# Charging_sch.net
KiCad netlist of a schematic drawn in Altium Designer
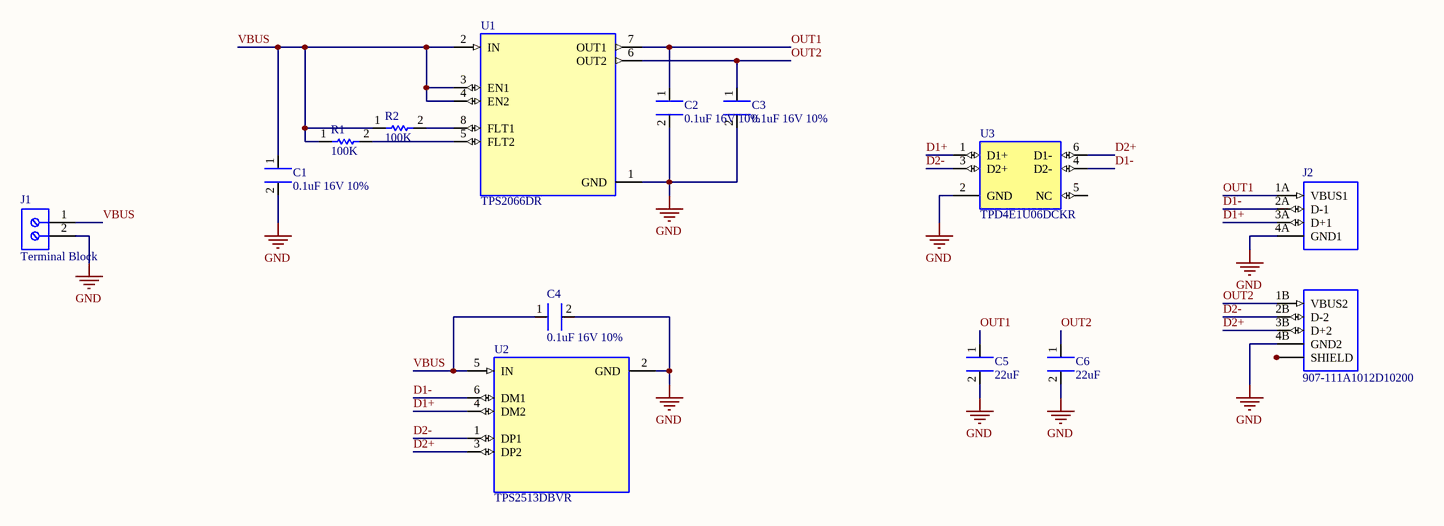
[diagram p0: Charging_sch.SchDoc]

(export (version "E")
  (design (tool "Eeschema 10.0.6"))
  (components
    (comp (ref "C1")
      (value "0.1uF 16V 10%")
      (footprint "CC0805KRX7R9BB104")
      (description "贴片电容（MLCC） 100nF ±10% 50V X7R 0805")
      (fields
        (field (name "MANUFACTURER") "Yageo")
        (field (name "MANUFACTURER PART NUMBER") "CC0805KRX7R9BB104")
      )
      (libsource (lib "Schlib2") (part "CC0805KRX7R9BB104"))
    )
    (comp (ref "C2")
      (value "0.1uF 16V 10%")
      (footprint "CC0805KRX7R9BB104")
      (description "贴片电容（MLCC） 100nF ±10% 50V X7R 0805")
      (fields
        (field (name "MANUFACTURER") "Yageo")
        (field (name "MANUFACTURER PART NUMBER") "CC0805KRX7R9BB104")
      )
      (libsource (lib "Schlib2") (part "CC0805KRX7R9BB104"))
    )
    (comp (ref "C3")
      (value "0.1uF 16V 10%")
      (footprint "CC0805KRX7R9BB104")
      (description "贴片电容（MLCC） 100nF ±10% 50V X7R 0805")
      (fields
        (field (name "MANUFACTURER") "Yageo")
        (field (name "MANUFACTURER PART NUMBER") "CC0805KRX7R9BB104")
      )
      (libsource (lib "Schlib2") (part "CC0805KRX7R9BB104"))
    )
    (comp (ref "C4")
      (value "0.1uF 16V 10%")
      (footprint "CC0805KRX7R9BB104")
      (description "贴片电容（MLCC） 100nF ±10% 50V X7R 0805")
      (fields
        (field (name "MANUFACTURER") "Yageo")
        (field (name "MANUFACTURER PART NUMBER") "CC0805KRX7R9BB104")
      )
      (libsource (lib "Schlib2") (part "CC0805KRX7R9BB104"))
    )
    (comp (ref "C5")
      (value "22uF")
      (footprint "RVT1C220M0405")
      (fields
        (field (name "MANUFACTURER") "ROQANG")
        (field (name "MANUFACTURER PART NUMBER") "RVT1C220M0405")
      )
      (libsource (lib "Schlib2") (part "RVT1C220M0405"))
    )
    (comp (ref "C6")
      (value "22uF")
      (footprint "RVT1C220M0405")
      (fields
        (field (name "MANUFACTURER") "ROQANG")
        (field (name "MANUFACTURER PART NUMBER") "RVT1C220M0405")
      )
      (libsource (lib "Schlib2") (part "RVT1C220M0405"))
    )
    (comp (ref "J1")
      (value "Terminal Block")
      (footprint "Terminal Block")
      (description "Conn Terminal Block F 2 POS 5mm Solder RA SMD 6A T/R")
      (fields
        (field (name "MANUFACTURER") "Wurth Electronics Midcom")
        (field (name "MANUFACTURER PART NUMBER") "691709710302")
      )
      (libsource (lib "Schlib1") (part "691709710302"))
    )
    (comp (ref "J2")
      (value "907-111A1012D10200")
      (footprint "907-111A1012D10200")
      (description "USB1035 Series 8 Position Dual Port Through Hole USB")
      (fields (field (name "MANUFACTURER") "Jing Extension of the Electronic Co."))
      (libsource (lib "Schlib2") (part "907-111A1012D10200"))
    )
    (comp (ref "R1")
      (value "100K")
      (footprint "ARG05FTC1003")
      (fields
        (field (name "MANUFACTURER") "Viking Tech")
        (field (name "MANUFACTURER PART NUMBER") "ARG05FTC1003")
      )
      (libsource (lib "Schlib2") (part "ARG05FTC1003"))
    )
    (comp (ref "R2")
      (value "100K")
      (footprint "ARG05FTC1003")
      (fields
        (field (name "MANUFACTURER") "Viking Tech")
        (field (name "MANUFACTURER PART NUMBER") "ARG05FTC1003")
      )
      (libsource (lib "Schlib2") (part "ARG05FTC1003"))
    )
    (comp (ref "U1")
      (value "TPS2066DR")
      (footprint "TPS2066DR")
      (description "Dual 1A, active-high, current-limited, power-distribution switches 8-SOIC -40 to 85")
      (fields (field (name "MANUFACTURER") "Texas Instruments"))
      (libsource (lib "Schlib2") (part "TPS2066DR"))
    )
    (comp (ref "U2")
      (value "TPS2513DBVR")
      (footprint "TPS2513DBVR")
      (description "USB Charging Port Controller Dual 5.5V 6-Pin SOT-23 T/R / IC USB PWR SW/CTRLR CHRG SOT23-6")
      (fields (field (name "MANUFACTURER") "Texas Instruments"))
      (libsource (lib "Schlib2") (part "TPS2513DBVR"))
    )
    (comp (ref "U3")
      (value "TPD4E1U06DCKR")
      (footprint "TPD4E1U06DCKR")
      (description "TVS DIODE 5.5VWM 15VC SC70-6")
      (fields (field (name "MANUFACTURER") "Texas Instruments"))
      (libsource (lib "Schlib2") (part "TPD4E1U06DCKR"))
    )
  )
  (nets
    (net (code "1") (name "/D1+") (class "Default")
      (node (ref "J2") (pin "3A") (pinfunction "D+1_3A") (pintype "bidirectional"))
      (node (ref "U2") (pin "4") (pinfunction "DM2_4") (pintype "bidirectional"))
      (node (ref "U3") (pin "1") (pinfunction "D1+_1") (pintype "bidirectional"))
    )
    (net (code "2") (name "/D1-") (class "Default")
      (node (ref "J2") (pin "2A") (pinfunction "D-1_2A") (pintype "bidirectional"))
      (node (ref "U2") (pin "6") (pinfunction "DM1_6") (pintype "bidirectional"))
      (node (ref "U3") (pin "4") (pinfunction "D2-_4") (pintype "bidirectional"))
    )
    (net (code "3") (name "/D2+") (class "Default")
      (node (ref "J2") (pin "3B") (pinfunction "D+2_3B") (pintype "bidirectional"))
      (node (ref "U2") (pin "3") (pinfunction "DP2_3") (pintype "bidirectional"))
      (node (ref "U3") (pin "6") (pinfunction "D1-_6") (pintype "bidirectional"))
    )
    (net (code "4") (name "/D2-") (class "Default")
      (node (ref "J2") (pin "2B") (pinfunction "D-2_2B") (pintype "bidirectional"))
      (node (ref "U2") (pin "1") (pinfunction "DP1_1") (pintype "bidirectional"))
      (node (ref "U3") (pin "3") (pinfunction "D2+_3") (pintype "bidirectional"))
    )
    (net (code "5") (name "/OUT1") (class "Default")
      (node (ref "C2") (pin "1") (pinfunction "1_1") (pintype "passive"))
      (node (ref "C5") (pin "1") (pinfunction "1_1") (pintype "passive"))
      (node (ref "J2") (pin "1A") (pinfunction "VBUS1_1A") (pintype "input"))
      (node (ref "U1") (pin "7") (pinfunction "OUT1_7") (pintype "output"))
    )
    (net (code "6") (name "/OUT2") (class "Default")
      (node (ref "C3") (pin "1") (pinfunction "1_1") (pintype "passive"))
      (node (ref "C6") (pin "1") (pinfunction "1_1") (pintype "passive"))
      (node (ref "J2") (pin "1B") (pinfunction "VBUS2_1B") (pintype "input"))
      (node (ref "U1") (pin "6") (pinfunction "OUT2_6") (pintype "output"))
    )
    (net (code "7") (name "/VBUS") (class "Default")
      (node (ref "C1") (pin "1") (pinfunction "1_1") (pintype "passive"))
      (node (ref "C4") (pin "1") (pinfunction "1_1") (pintype "passive"))
      (node (ref "J1") (pin "1") (pinfunction "1_1") (pintype "passive"))
      (node (ref "R1") (pin "1") (pinfunction "1_1") (pintype "passive"))
      (node (ref "R2") (pin "1") (pinfunction "1_1") (pintype "passive"))
      (node (ref "U1") (pin "2") (pinfunction "IN_2") (pintype "input"))
      (node (ref "U1") (pin "3") (pinfunction "EN1_3") (pintype "bidirectional"))
      (node (ref "U1") (pin "4") (pinfunction "EN2_4") (pintype "bidirectional"))
      (node (ref "U2") (pin "5") (pinfunction "IN_5") (pintype "input"))
    )
    (net (code "8") (name "GND") (class "Default")
      (node (ref "C1") (pin "2") (pinfunction "2_2") (pintype "passive"))
      (node (ref "C2") (pin "2") (pinfunction "2_2") (pintype "passive"))
      (node (ref "C3") (pin "2") (pinfunction "2_2") (pintype "passive"))
      (node (ref "C4") (pin "2") (pinfunction "2_2") (pintype "passive"))
      (node (ref "C5") (pin "2") (pinfunction "2_2") (pintype "passive"))
      (node (ref "C6") (pin "2") (pinfunction "2_2") (pintype "passive"))
      (node (ref "J1") (pin "2") (pinfunction "2_2") (pintype "passive"))
      (node (ref "J2") (pin "4A") (pinfunction "GND1_4A") (pintype "power_in"))
      (node (ref "J2") (pin "4B") (pinfunction "GND2_4B") (pintype "power_in"))
      (node (ref "U1") (pin "1") (pinfunction "GND_1") (pintype "power_in"))
      (node (ref "U2") (pin "2") (pinfunction "GND_2") (pintype "power_in"))
      (node (ref "U3") (pin "2") (pinfunction "GND_2") (pintype "power_in"))
    )
    (net (code "9") (name "Net-(J2-SHIELD-Pad10)") (class "Default")
      (node (ref "J2") (pin "10") (pinfunction "SHIELD_10") (pintype "power_in"))
      (node (ref "J2") (pin "11") (pinfunction "SHIELD_11") (pintype "power_in"))
      (node (ref "J2") (pin "12") (pinfunction "SHIELD_12") (pintype "power_in"))
      (node (ref "J2") (pin "9") (pinfunction "SHIELD_9") (pintype "power_in"))
    )
    (net (code "10") (name "Net-(U1-FLT1)") (class "Default")
      (node (ref "R2") (pin "2") (pinfunction "2_2") (pintype "passive"))
      (node (ref "U1") (pin "8") (pinfunction "FLT1_8") (pintype "bidirectional"))
    )
    (net (code "11") (name "Net-(U1-FLT2)") (class "Default")
      (node (ref "R1") (pin "2") (pinfunction "2_2") (pintype "passive"))
      (node (ref "U1") (pin "5") (pinfunction "FLT2_5") (pintype "bidirectional"))
    )
    (net (code "12") (name "unconnected-(U3-NC-Pad5)") (class "Default")
      (node (ref "U3") (pin "5") (pinfunction "NC_5") (pintype "bidirectional"))
    )
  )
)
